# ESP8266-12x.net
KiCad netlist of a schematic drawn in Altium Designer
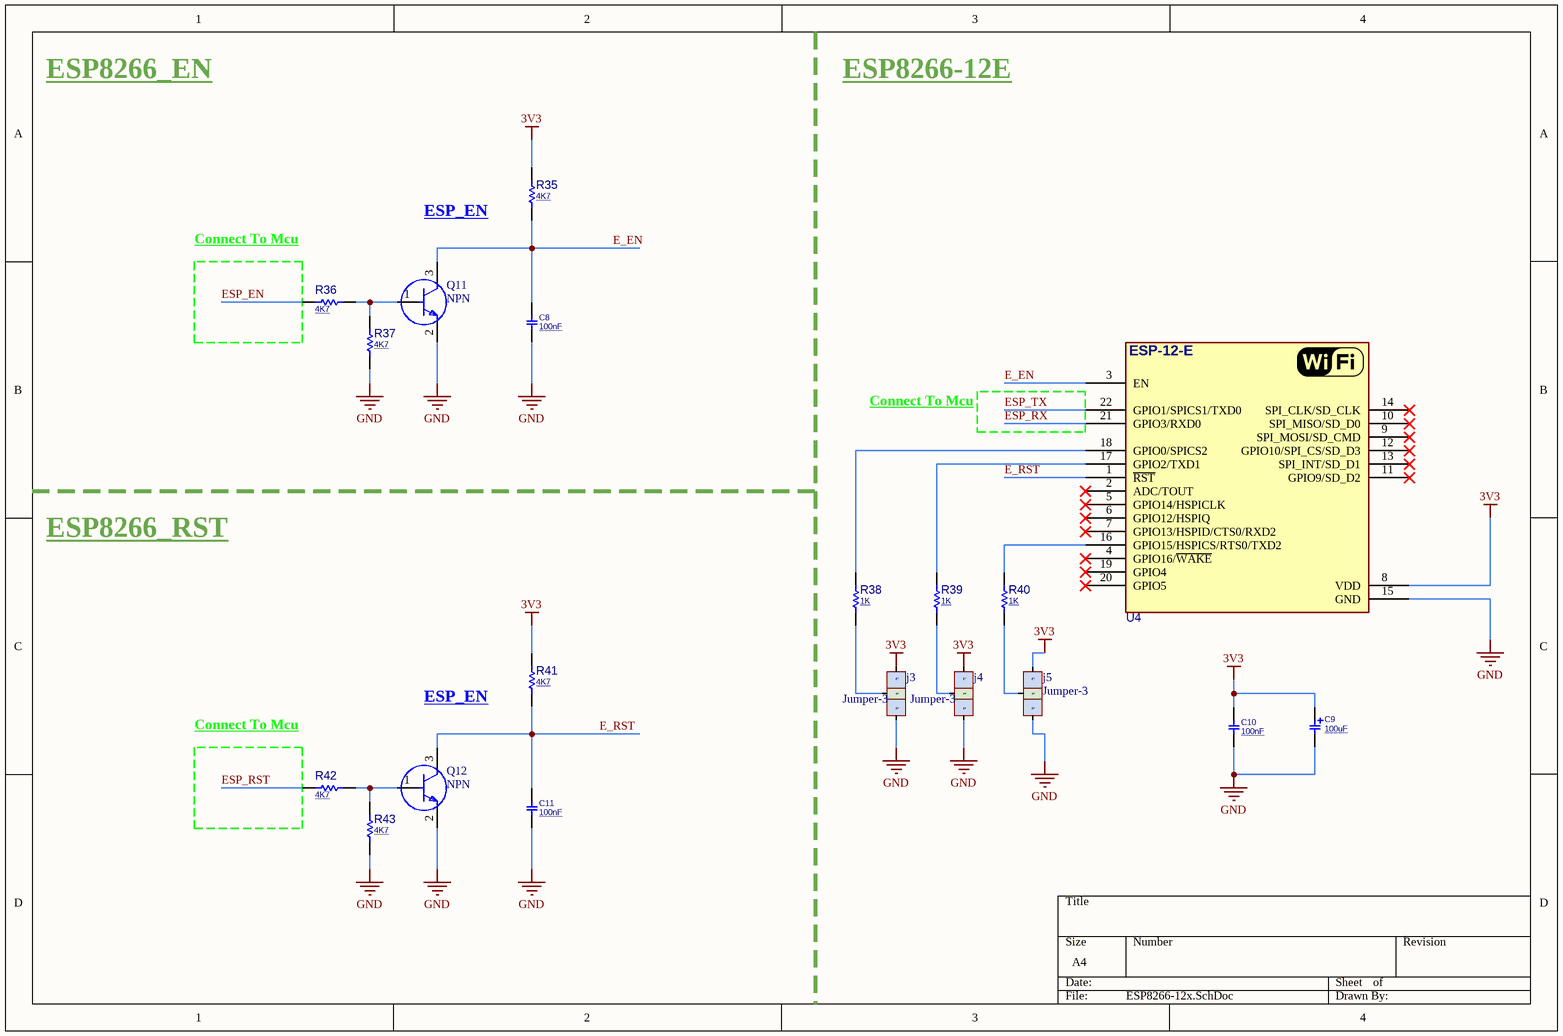
[diagram p0: ESP8266-12x.SchDoc]

(export (version "E")
  (design (tool "Eeschema 10.0.6"))
  (components
    (comp (ref "C8")
      (value "100nF")
      (footprint "C0603")
      (description "CAP, MLCC, -F, -V, MATERIAL, -%, 0201")
      (fields (field (name "MANF_P#") "MANF_PART#"))
      (libsource (lib "passive_smd") (part "CAP_SMD_MLCC_0603"))
    )
    (comp (ref "C9")
      (value "100uF")
      (footprint "C_TN_3216")
      (description "CAP, SMD, TAN,")
      (fields (field (name "Comment") "4.7uF"))
      (libsource (lib "passive_smd") (part "CAP_SMD_TAN_3216"))
    )
    (comp (ref "C10")
      (value "100nF")
      (footprint "C0603")
      (description "CAP, MLCC, -F, -V, MATERIAL, -%, 0201")
      (fields (field (name "MANF_P#") "MANF_PART#"))
      (libsource (lib "passive_smd") (part "CAP_SMD_MLCC_0603"))
    )
    (comp (ref "C11")
      (value "100nF")
      (footprint "C0603")
      (description "CAP, MLCC, -F, -V, MATERIAL, -%, 0201")
      (fields (field (name "MANF_P#") "MANF_PART#"))
      (libsource (lib "passive_smd") (part "CAP_SMD_MLCC_0603"))
    )
    (comp (ref "j3") (value "Jumper-3") (footprint "jumper-3") (libsource (lib "jumper") (part "Jumper-3")))
    (comp (ref "j4") (value "Jumper-3") (footprint "jumper-3") (libsource (lib "jumper") (part "Jumper-3")))
    (comp (ref "j5") (value "Jumper-3") (footprint "jumper-3") (libsource (lib "jumper") (part "Jumper-3")))
    (comp (ref "Q11")
      (value "NPN")
      (footprint "FP-SOT23-IPC_A")
      (libsource (lib "NPN-SOT-23") (part "CMP-2000-04931-2"))
    )
    (comp (ref "Q12")
      (value "NPN")
      (footprint "FP-SOT23-IPC_A")
      (libsource (lib "NPN-SOT-23") (part "CMP-2000-04931-2"))
    )
    (comp (ref "R35")
      (value "4K7")
      (footprint "R0603")
      (description "RESISTOR, SMD")
      (libsource (lib "passive_smd") (part "RES_SMD"))
    )
    (comp (ref "R36")
      (value "4K7")
      (footprint "R0603")
      (description "RESISTOR, SMD")
      (libsource (lib "passive_smd") (part "RES_SMD"))
    )
    (comp (ref "R37")
      (value "4K7")
      (footprint "R0603")
      (description "RESISTOR, SMD")
      (libsource (lib "passive_smd") (part "RES_SMD"))
    )
    (comp (ref "R38")
      (value "1K")
      (footprint "R0603")
      (description "RESISTOR, SMD")
      (libsource (lib "passive_smd") (part "RES_SMD"))
    )
    (comp (ref "R39")
      (value "1K")
      (footprint "R0603")
      (description "RESISTOR, SMD")
      (libsource (lib "passive_smd") (part "RES_SMD"))
    )
    (comp (ref "R40")
      (value "1K")
      (footprint "R0603")
      (description "RESISTOR, SMD")
      (libsource (lib "passive_smd") (part "RES_SMD"))
    )
    (comp (ref "R41")
      (value "4K7")
      (footprint "R0603")
      (description "RESISTOR, SMD")
      (libsource (lib "passive_smd") (part "RES_SMD"))
    )
    (comp (ref "R42")
      (value "4K7")
      (footprint "R0603")
      (description "RESISTOR, SMD")
      (libsource (lib "passive_smd") (part "RES_SMD"))
    )
    (comp (ref "R43")
      (value "4K7")
      (footprint "R0603")
      (description "RESISTOR, SMD")
      (libsource (lib "passive_smd") (part "RES_SMD"))
    )
    (comp (ref "U4")
      (value "~")
      (footprint "ESP8266_ESP12E")
      (description "ESP8266 ESP-12 Wi-Fi Module")
      (libsource (lib "Module") (part "ESP8266 ESP-12-E"))
    )
  )
  (nets
    (net (code "1") (name "/ESP_EN") (class "Default")
      (node (ref "R36") (pin "1") (pinfunction "1_1") (pintype "passive"))
    )
    (net (code "2") (name "/ESP_RST") (class "Default")
      (node (ref "R42") (pin "1") (pinfunction "1_1") (pintype "passive"))
    )
    (net (code "3") (name "/ESP_RX") (class "Default")
      (node (ref "U4") (pin "21") (pinfunction "GPIO3/RXD0_21") (pintype "passive"))
    )
    (net (code "4") (name "/ESP_TX") (class "Default")
      (node (ref "U4") (pin "22") (pinfunction "GPIO1/SPICS1/TXD0_22") (pintype "passive"))
    )
    (net (code "5") (name "/E_EN") (class "Default")
      (node (ref "C8") (pin "2") (pinfunction "2_2") (pintype "passive"))
      (node (ref "Q11") (pin "3") (pinfunction "C_3") (pintype "passive"))
      (node (ref "R35") (pin "1") (pinfunction "1_1") (pintype "passive"))
      (node (ref "U4") (pin "3") (pinfunction "EN_3") (pintype "passive"))
    )
    (net (code "6") (name "/E_RST") (class "Default")
      (node (ref "C11") (pin "2") (pinfunction "2_2") (pintype "passive"))
      (node (ref "Q12") (pin "3") (pinfunction "C_3") (pintype "passive"))
      (node (ref "R41") (pin "1") (pinfunction "1_1") (pintype "passive"))
      (node (ref "U4") (pin "1") (pinfunction "~{RST}_1") (pintype "passive"))
    )
    (net (code "7") (name "3V3") (class "Default")
      (node (ref "C10") (pin "2") (pinfunction "2_2") (pintype "passive"))
      (node (ref "C9") (pin "1") (pinfunction "1_1") (pintype "passive"))
      (node (ref "R35") (pin "2") (pinfunction "2_2") (pintype "passive"))
      (node (ref "R41") (pin "2") (pinfunction "2_2") (pintype "passive"))
      (node (ref "U4") (pin "8") (pinfunction "VDD_8") (pintype "passive"))
      (node (ref "j3") (pin "3") (pinfunction "3_3") (pintype "passive"))
      (node (ref "j4") (pin "3") (pinfunction "3_3") (pintype "passive"))
      (node (ref "j5") (pin "3") (pinfunction "3_3") (pintype "passive"))
    )
    (net (code "8") (name "GND") (class "Default")
      (node (ref "C10") (pin "1") (pinfunction "1_1") (pintype "passive"))
      (node (ref "C11") (pin "1") (pinfunction "1_1") (pintype "passive"))
      (node (ref "C8") (pin "1") (pinfunction "1_1") (pintype "passive"))
      (node (ref "C9") (pin "2") (pinfunction "2_2") (pintype "passive"))
      (node (ref "Q11") (pin "2") (pinfunction "E_2") (pintype "passive"))
      (node (ref "Q12") (pin "2") (pinfunction "E_2") (pintype "passive"))
      (node (ref "R37") (pin "1") (pinfunction "1_1") (pintype "passive"))
      (node (ref "R43") (pin "1") (pinfunction "1_1") (pintype "passive"))
      (node (ref "U4") (pin "15") (pinfunction "GND_15") (pintype "passive"))
      (node (ref "j3") (pin "1") (pinfunction "1_1") (pintype "passive"))
      (node (ref "j4") (pin "1") (pinfunction "1_1") (pintype "passive"))
      (node (ref "j5") (pin "1") (pinfunction "1_1") (pintype "passive"))
    )
    (net (code "9") (name "Net-(Q11-B)") (class "Default")
      (node (ref "Q11") (pin "1") (pinfunction "B_1") (pintype "passive"))
      (node (ref "R36") (pin "2") (pinfunction "2_2") (pintype "passive"))
      (node (ref "R37") (pin "2") (pinfunction "2_2") (pintype "passive"))
    )
    (net (code "10") (name "Net-(Q12-B)") (class "Default")
      (node (ref "Q12") (pin "1") (pinfunction "B_1") (pintype "passive"))
      (node (ref "R42") (pin "2") (pinfunction "2_2") (pintype "passive"))
      (node (ref "R43") (pin "2") (pinfunction "2_2") (pintype "passive"))
    )
    (net (code "11") (name "Net-(R38-Pad1)") (class "Default")
      (node (ref "R38") (pin "1") (pinfunction "1_1") (pintype "passive"))
      (node (ref "j3") (pin "2") (pinfunction "2_2") (pintype "passive"))
    )
    (net (code "12") (name "Net-(R39-Pad1)") (class "Default")
      (node (ref "R39") (pin "1") (pinfunction "1_1") (pintype "passive"))
      (node (ref "j4") (pin "2") (pinfunction "2_2") (pintype "passive"))
    )
    (net (code "13") (name "Net-(R40-Pad1)") (class "Default")
      (node (ref "R40") (pin "1") (pinfunction "1_1") (pintype "passive"))
      (node (ref "j5") (pin "2") (pinfunction "2_2") (pintype "passive"))
    )
    (net (code "14") (name "Net-(U4-GPIO0{slash}SPICS2)") (class "Default")
      (node (ref "R38") (pin "2") (pinfunction "2_2") (pintype "passive"))
      (node (ref "U4") (pin "18") (pinfunction "GPIO0/SPICS2_18") (pintype "passive"))
    )
    (net (code "15") (name "Net-(U4-GPIO2{slash}TXD1)") (class "Default")
      (node (ref "R39") (pin "2") (pinfunction "2_2") (pintype "passive"))
      (node (ref "U4") (pin "17") (pinfunction "GPIO2/TXD1_17") (pintype "passive"))
    )
    (net (code "16") (name "Net-(U4-GPIO15{slash}HSPICS{slash}RTS0{slash}TXD2)") (class "Default")
      (node (ref "R40") (pin "2") (pinfunction "2_2") (pintype "passive"))
      (node (ref "U4") (pin "16") (pinfunction "GPIO15/HSPICS/RTS0/TXD2_16") (pintype "passive"))
    )
    (net (code "17") (name "unconnected-(U4-ADC{slash}TOUT-Pad2)") (class "Default")
      (node (ref "U4") (pin "2") (pinfunction "ADC/TOUT_2") (pintype "passive+no_connect"))
    )
    (net (code "18") (name "unconnected-(U4-GPIO4-Pad19)") (class "Default")
      (node (ref "U4") (pin "19") (pinfunction "GPIO4_19") (pintype "passive+no_connect"))
    )
    (net (code "19") (name "unconnected-(U4-GPIO5-Pad20)") (class "Default")
      (node (ref "U4") (pin "20") (pinfunction "GPIO5_20") (pintype "passive+no_connect"))
    )
    (net (code "20") (name "unconnected-(U4-GPIO9{slash}SD_D2-Pad11)") (class "Default")
      (node (ref "U4") (pin "11") (pinfunction "GPIO9/SD_D2_11") (pintype "passive+no_connect"))
    )
    (net (code "21") (name "unconnected-(U4-GPIO10{slash}SPI_CS{slash}SD_D3-Pad12)") (class "Default")
      (node (ref "U4") (pin "12") (pinfunction "GPIO10/SPI_CS/SD_D3_12") (pintype "passive+no_connect"))
    )
    (net (code "22") (name "unconnected-(U4-GPIO12{slash}HSPIQ-Pad6)") (class "Default")
      (node (ref "U4") (pin "6") (pinfunction "GPIO12/HSPIQ_6") (pintype "passive+no_connect"))
    )
    (net (code "23") (name "unconnected-(U4-GPIO13{slash}HSPID{slash}CTS0{slash}RXD2-Pad7)") (class "Default")
      (node (ref "U4") (pin "7") (pinfunction "GPIO13/HSPID/CTS0/RXD2_7") (pintype "passive+no_connect"))
    )
    (net (code "24") (name "unconnected-(U4-GPIO14{slash}HSPICLK-Pad5)") (class "Default")
      (node (ref "U4") (pin "5") (pinfunction "GPIO14/HSPICLK_5") (pintype "passive+no_connect"))
    )
    (net (code "25") (name "unconnected-(U4-GPIO16{slash}~{WAKE}-Pad4)") (class "Default")
      (node (ref "U4") (pin "4") (pinfunction "GPIO16/~{WAKE}_4") (pintype "passive+no_connect"))
    )
    (net (code "26") (name "unconnected-(U4-SPI_CLK{slash}SD_CLK-Pad14)") (class "Default")
      (node (ref "U4") (pin "14") (pinfunction "SPI_CLK/SD_CLK_14") (pintype "passive+no_connect"))
    )
    (net (code "27") (name "unconnected-(U4-SPI_INT{slash}SD_D1-Pad13)") (class "Default")
      (node (ref "U4") (pin "13") (pinfunction "SPI_INT/SD_D1_13") (pintype "passive+no_connect"))
    )
    (net (code "28") (name "unconnected-(U4-SPI_MISO{slash}SD_D0-Pad10)") (class "Default")
      (node (ref "U4") (pin "10") (pinfunction "SPI_MISO/SD_D0_10") (pintype "passive+no_connect"))
    )
    (net (code "29") (name "unconnected-(U4-SPI_MOSI{slash}SD_CMD-Pad9)") (class "Default")
      (node (ref "U4") (pin "9") (pinfunction "SPI_MOSI/SD_CMD_9") (pintype "passive+no_connect"))
    )
  )
)
